# Sheet1.net
KiCad netlist of a schematic drawn in Altium Designer
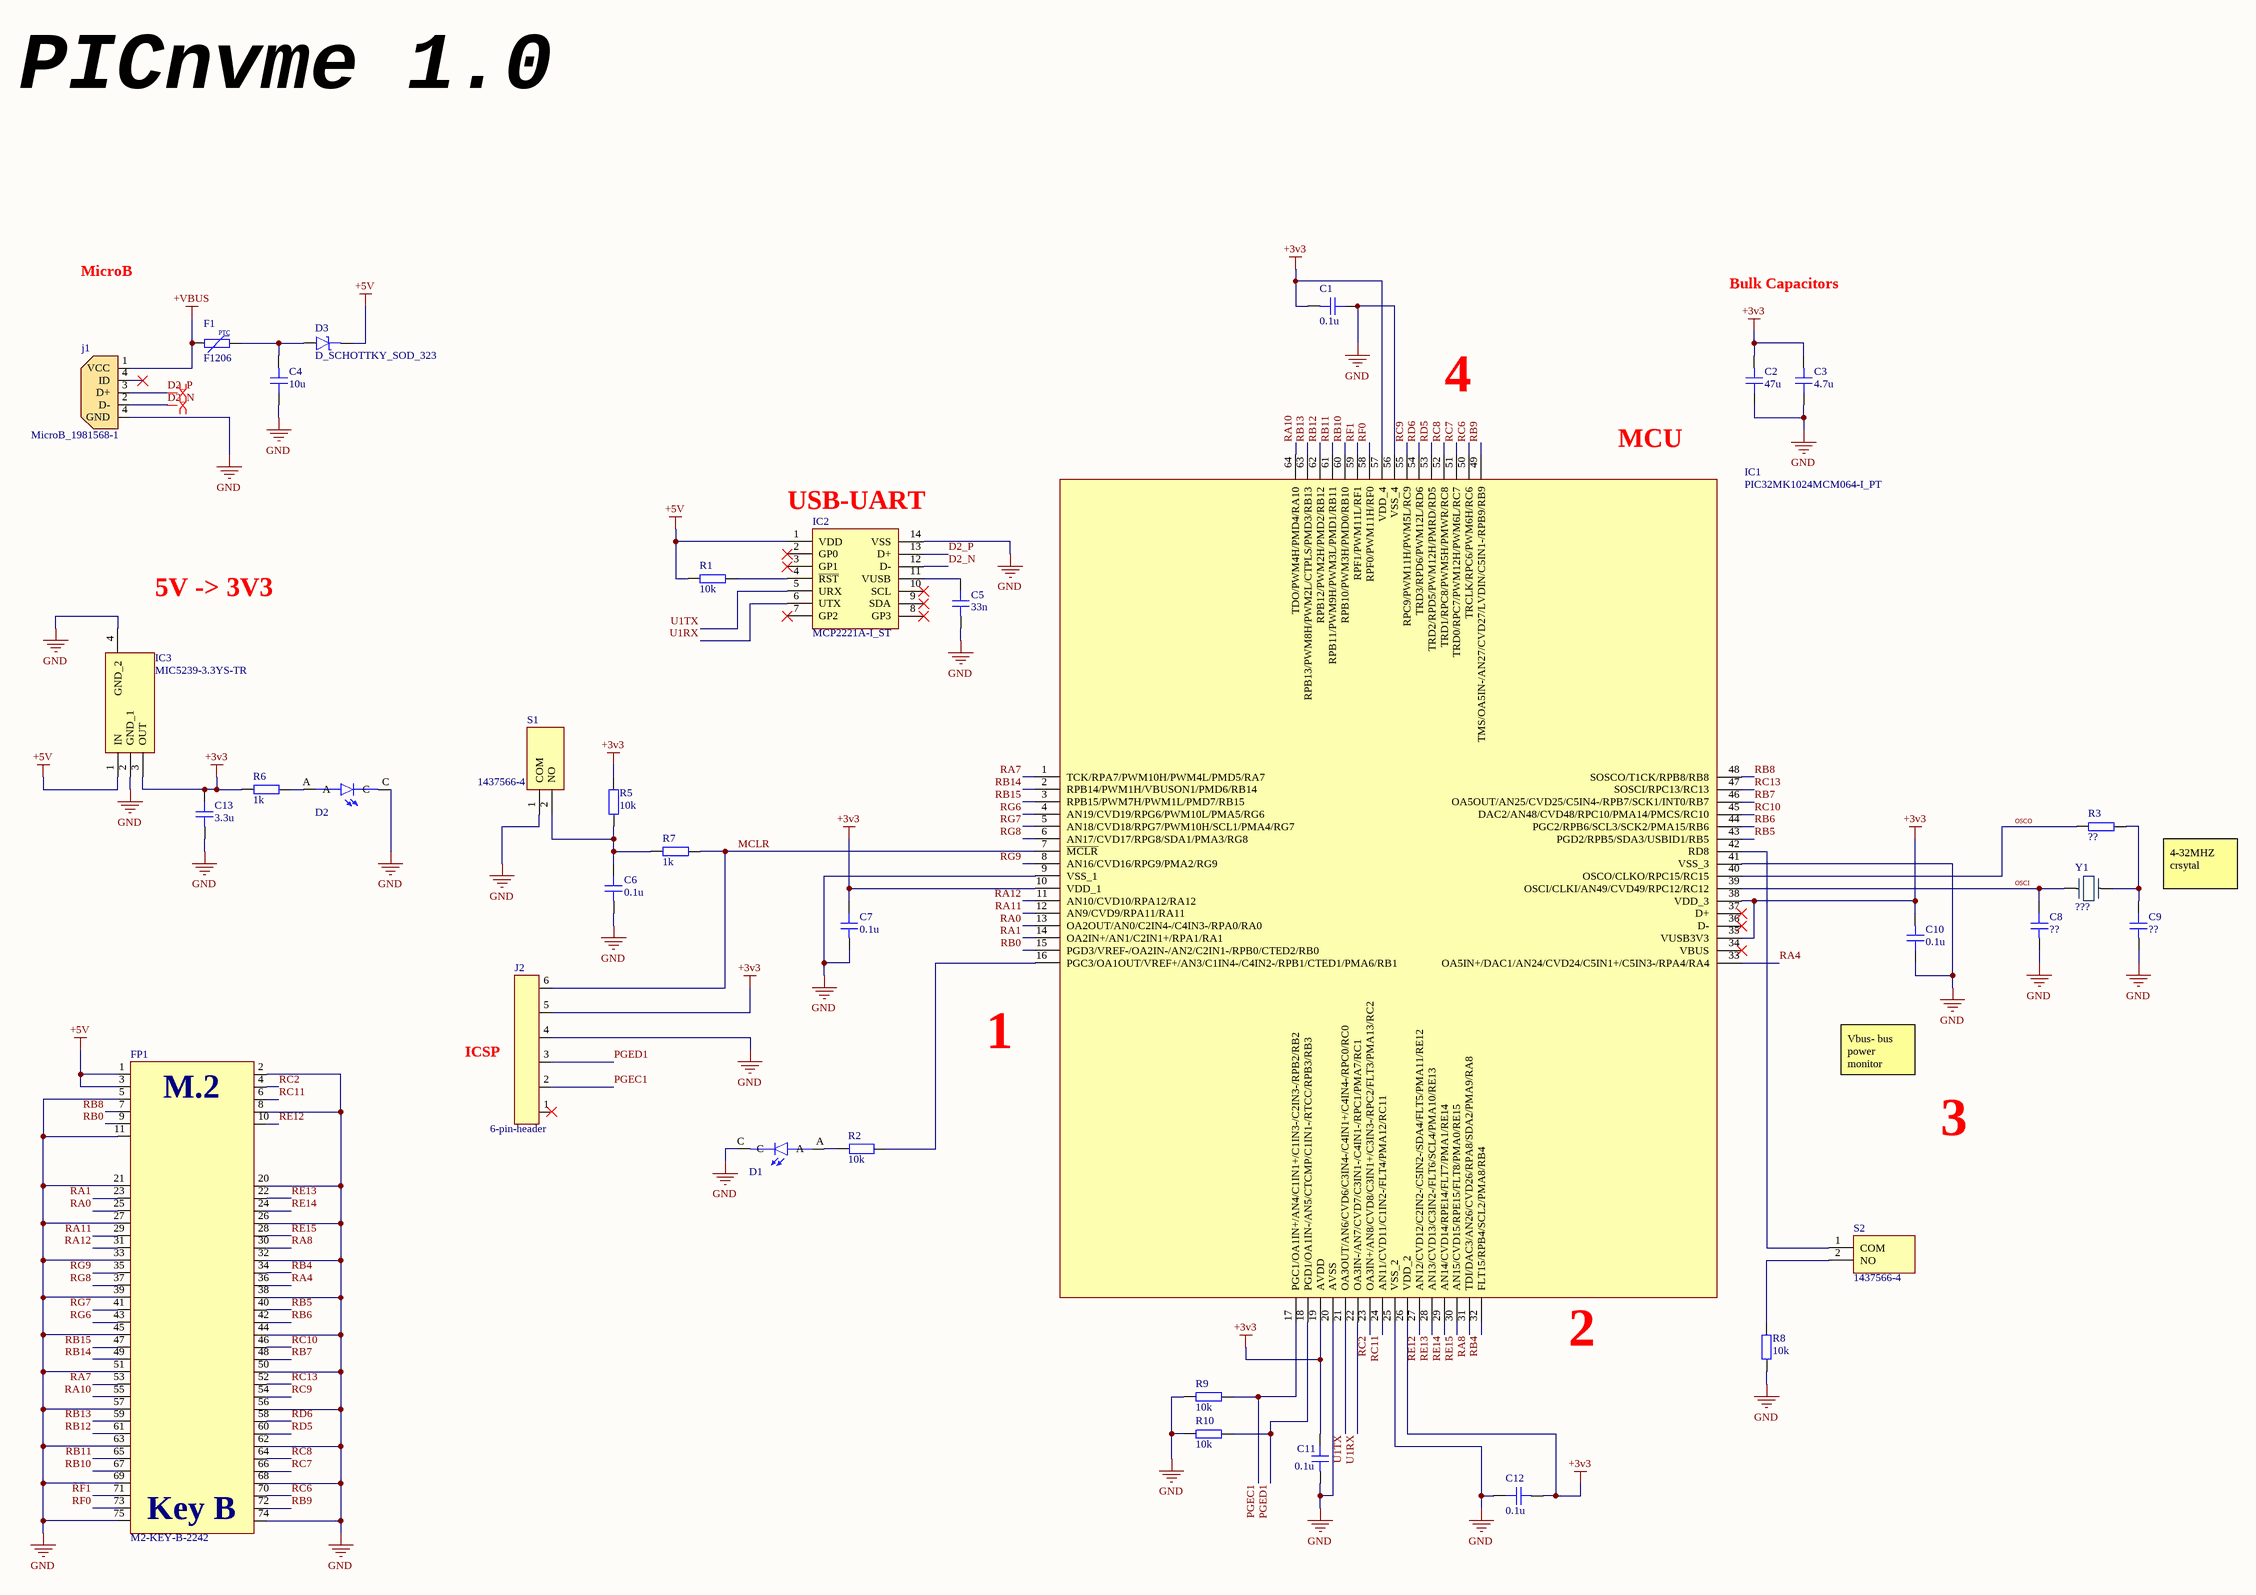
[diagram p0: Sheet1.SchDoc]

(export (version "E")
  (design (tool "Eeschema 10.0.6"))
  (components
    (comp (ref "C1")
      (value "0.1u")
      (footprint "CAP_0805")
      (description "Capacitor SMD 0805 16V")
      (libsource (lib "Pedro_Integrated_Library") (part "CAP_0805_16V"))
    )
    (comp (ref "C2")
      (value "47u")
      (footprint "CAP_0805")
      (description "Capacitor SMD 0805 16V")
      (libsource (lib "Pedro_Integrated_Library") (part "CAP_0805_16V"))
    )
    (comp (ref "C3")
      (value "4.7u")
      (footprint "CAP_0805")
      (description "Capacitor SMD 0805 16V")
      (libsource (lib "Pedro_Integrated_Library") (part "CAP_0805_16V"))
    )
    (comp (ref "C4")
      (value "10u")
      (footprint "CAP_0805")
      (description "Capacitor SMD 0805 10V")
      (libsource (lib "Schematic-Lib-PhilsLab") (part "CAP_0805_10V"))
    )
    (comp (ref "C5")
      (value "33n")
      (footprint "CAP_0805")
      (description "Capacitor SMD 0805 10V")
      (libsource (lib "Schematic-Lib-PhilsLab") (part "CAP_0805_10V"))
    )
    (comp (ref "C6")
      (value "0.1u")
      (footprint "CAP_0805")
      (description "Capacitor SMD 0805 16V")
      (libsource (lib "Pedro_Integrated_Library") (part "CAP_0805_16V"))
    )
    (comp (ref "C7")
      (value "0.1u")
      (footprint "CAP_0805")
      (description "Capacitor SMD 0805 16V")
      (libsource (lib "Pedro_Integrated_Library") (part "CAP_0805_16V"))
    )
    (comp (ref "C8")
      (value "??")
      (footprint "CAP_0805")
      (description "Capacitor SMD 0805 16V")
      (libsource (lib "Pedro_Integrated_Library") (part "CAP_0805_16V"))
    )
    (comp (ref "C9")
      (value "??")
      (footprint "CAP_0805")
      (description "Capacitor SMD 0805 16V")
      (libsource (lib "Pedro_Integrated_Library") (part "CAP_0805_16V"))
    )
    (comp (ref "C10")
      (value "0.1u")
      (footprint "CAP_0805")
      (description "Capacitor SMD 0805 16V")
      (libsource (lib "Pedro_Integrated_Library") (part "CAP_0805_16V"))
    )
    (comp (ref "C11")
      (value "0.1u")
      (footprint "CAP_0805")
      (description "Capacitor SMD 0805 16V")
      (libsource (lib "Pedro_Integrated_Library") (part "CAP_0805_16V"))
    )
    (comp (ref "C12")
      (value "0.1u")
      (footprint "CAP_0805")
      (description "Capacitor SMD 0805 16V")
      (libsource (lib "Pedro_Integrated_Library") (part "CAP_0805_16V"))
    )
    (comp (ref "C13")
      (value "3.3u")
      (footprint "CAP_0805")
      (description "Capacitor SMD 0805 16V")
      (libsource (lib "Pedro_Integrated_Library") (part "CAP_0805_16V"))
    )
    (comp (ref "D1")
      (value "SML-LXT0805IW-TR")
      (footprint "LEDC2012X120N")
      (description "Red - LED Indication - Discrete 2V 0805 (2012 Metric)")
      (fields (field (name "MF") "Lumex Opto/Components"))
      (libsource (lib "SML-LXT0805IW-TR") (part "SML-LXT0805IW-TR"))
    )
    (comp (ref "D2")
      (value "SML-LXT0805IW-TR")
      (footprint "LEDC2012X120N")
      (description "Red - LED Indication - Discrete 2V 0805 (2012 Metric)")
      (fields (field (name "MF") "Lumex Opto/Components"))
      (libsource (lib "SML-LXT0805IW-TR") (part "SML-LXT0805IW-TR"))
    )
    (comp (ref "D3")
      (value "D_SCHOTTKY_SOD_323")
      (footprint "SOD-323")
      (description "Diode Schottky SMD SOD-323")
      (libsource (lib "PhilsLab") (part "D_SCHOTTKY_SOD_323"))
    )
    (comp (ref "F1")
      (value "F1206")
      (footprint "FUSE_1206")
      (description "Fuse PPTC SMD 1206")
      (libsource (lib "Schematic-Lib-PhilsLab") (part "FUSE_PPTC_1206"))
    )
    (comp (ref "FP1")
      (value "M2-KEY-B-2242")
      (footprint "M2-KEY-B-2242")
      (description "M.2 Key B 22x42 Footprint")
      (libsource (lib "PhilsLab") (part "M2-KEY-B-2242"))
    )
    (comp (ref "IC1")
      (value "PIC32MK1024MCM064-I_PT")
      (footprint "QFP50P1200X1200X120-64N")
      (description "Integrated Circuit")
      (fields
        (field (name "MANUFACTURER_PART_NUMBER") "PIC32MK1024MCM064-I/PT")
        (field (name "MOUSER PART NUMBER") "579-2MK1024MCM064IPT")
      )
      (libsource (lib "Pedro_Integrated_Library") (part "PIC32MK1024MCM064-I_PT"))
    )
    (comp (ref "IC2")
      (value "MCP2221A-I_ST")
      (footprint "Pedro_pcb_lib:SOP65P640X120-14N")
      (description "Integrated Circuit")
      (fields
        (field (name "MANUFACTURER_PART_NUMBER") "MCP2221A-I/ST")
        (field (name "MOUSER PART NUMBER") "579-MCP2221A-I/ST")
      )
      (libsource (lib "*") (part "MCP2221A-I_ST"))
    )
    (comp (ref "IC3")
      (value "MIC5239-3.3YS-TR")
      (footprint "Pedro_pcb_lib:SOT230P700X180-4N")
      (description "Integrated Circuit")
      (fields (field (name "MOUSER PART NUMBER") "998-MIC5239-3.3YSTR"))
      (libsource (lib "*") (part "MIC5239-3.3YS-TR"))
    )
    (comp (ref "j1")
      (value "MicroB_1981568-1")
      (footprint "1981568-1")
      (libsource (lib "Pedro_Integrated_Library") (part "Micro_B"))
    )
    (comp (ref "J2")
      (value "6-pin-header")
      (footprint "G800W302018EU")
      (description "Pin Header 6 Position 2.54mm Pitch")
      (fields
        (field (name "MANUFACTURER") "Amphenol")
        (field (name "MANUFACTURER PART NUMBER") "G800W302018EU")
      )
      (libsource (lib "PhilsLab") (part "G800W302018EU"))
    )
    (comp (ref "R1")
      (value "10k")
      (footprint "RES_0805")
      (description "Resistor SMD 0805")
      (libsource (lib "Pedro_Integrated_Library") (part "RES_0805"))
    )
    (comp (ref "R2")
      (value "10k")
      (footprint "RES_0805")
      (description "Resistor SMD 0805")
      (libsource (lib "Pedro_Integrated_Library") (part "RES_0805"))
    )
    (comp (ref "R3")
      (value "??")
      (footprint "RES_0805")
      (description "Resistor SMD 0805")
      (libsource (lib "Pedro_Integrated_Library") (part "RES_0805"))
    )
    (comp (ref "R5")
      (value "10k")
      (footprint "RES_0805")
      (description "Resistor SMD 0805")
      (libsource (lib "Pedro_Integrated_Library") (part "RES_0805"))
    )
    (comp (ref "R6")
      (value "1k")
      (footprint "RES_0805")
      (description "Resistor SMD 0805")
      (libsource (lib "Pedro_Integrated_Library") (part "RES_0805"))
    )
    (comp (ref "R7")
      (value "1k")
      (footprint "RES_0805")
      (description "Resistor SMD 0805")
      (libsource (lib "Pedro_Integrated_Library") (part "RES_0805"))
    )
    (comp (ref "R8")
      (value "10k")
      (footprint "RES_0805")
      (description "Resistor SMD 0805")
      (libsource (lib "Pedro_Integrated_Library") (part "RES_0805"))
    )
    (comp (ref "R9")
      (value "10k")
      (footprint "RES_0805")
      (description "Resistor SMD 0805")
      (libsource (lib "Pedro_Integrated_Library") (part "RES_0805"))
    )
    (comp (ref "R10")
      (value "10k")
      (footprint "RES_0805")
      (description "Resistor SMD 0805")
      (libsource (lib "Pedro_Integrated_Library") (part "RES_0805"))
    )
    (comp (ref "S1")
      (value "1437566-4")
      (footprint "Pedro_pcb_lib:14375664")
      (description "Switch")
      (libsource (lib "Pedro_sch_lib") (part "1437566-4"))
    )
    (comp (ref "S2")
      (value "1437566-4")
      (footprint "Pedro_pcb_lib:14375664")
      (description "Switch")
      (libsource (lib "") (part "1437566-4_1"))
    )
    (comp (ref "Y1")
      (value "???")
      (footprint "ABM38000MHZC4T")
      (libsource (lib "Pedro_Integrated_Library") (part "Crystal_SMD"))
    )
  )
  (nets
    (net (code "1") (name "+3v3") (class "Default")
      (node (ref "C1") (pin "1") (pinfunction "1_1") (pintype "passive"))
      (node (ref "C10") (pin "1") (pinfunction "1_1") (pintype "passive"))
      (node (ref "C11") (pin "2") (pinfunction "2_2") (pintype "passive"))
      (node (ref "C12") (pin "1") (pinfunction "1_1") (pintype "passive"))
      (node (ref "C13") (pin "2") (pinfunction "2_2") (pintype "passive"))
      (node (ref "C2") (pin "1") (pinfunction "1_1") (pintype "passive"))
      (node (ref "C3") (pin "1") (pinfunction "1_1") (pintype "passive"))
      (node (ref "C7") (pin "2") (pinfunction "2_2") (pintype "passive"))
      (node (ref "IC1") (pin "10") (pinfunction "VDD_1_10") (pintype "passive"))
      (node (ref "IC1") (pin "19") (pinfunction "AVDD_19") (pintype "passive"))
      (node (ref "IC1") (pin "26") (pinfunction "VDD_2_26") (pintype "passive"))
      (node (ref "IC1") (pin "35") (pinfunction "VUSB3V3_35") (pintype "passive"))
      (node (ref "IC1") (pin "38") (pinfunction "VDD_3_38") (pintype "passive"))
      (node (ref "IC1") (pin "57") (pinfunction "VDD_4_57") (pintype "passive"))
      (node (ref "IC3") (pin "3") (pinfunction "OUT_3") (pintype "passive"))
      (node (ref "J2") (pin "5") (pinfunction "5_5") (pintype "passive"))
      (node (ref "R5") (pin "1") (pinfunction "1_1") (pintype "passive"))
      (node (ref "R6") (pin "2") (pinfunction "2_2") (pintype "passive"))
    )
    (net (code "2") (name "+5V") (class "Default")
      (node (ref "D3") (pin "K") (pinfunction "K_K") (pintype "passive"))
      (node (ref "FP1") (pin "1") (pintype "passive"))
      (node (ref "FP1") (pin "3") (pintype "passive"))
      (node (ref "IC2") (pin "1") (pinfunction "VDD_1") (pintype "passive"))
      (node (ref "IC3") (pin "1") (pinfunction "IN_1") (pintype "passive"))
      (node (ref "R1") (pin "1") (pinfunction "1_1") (pintype "passive"))
    )
    (net (code "3") (name "+VBUS") (class "Default")
      (node (ref "F1") (pin "1") (pinfunction "1_1") (pintype "passive"))
      (node (ref "j1") (pin "1") (pinfunction "VCC_1") (pintype "power_in"))
    )
    (net (code "4") (name "/D2_N") (class "Default")
      (node (ref "IC2") (pin "12") (pinfunction "D-_12") (pintype "passive"))
      (node (ref "j1") (pin "2") (pinfunction "D-_2") (pintype "bidirectional"))
    )
    (net (code "5") (name "/D2_P") (class "Default")
      (node (ref "IC2") (pin "13") (pinfunction "D+_13") (pintype "passive"))
      (node (ref "j1") (pin "3") (pinfunction "D+_3") (pintype "bidirectional"))
    )
    (net (code "6") (name "/MCLR") (class "Default")
      (node (ref "IC1") (pin "7") (pinfunction "~{MCLR}_7") (pintype "passive"))
      (node (ref "J2") (pin "6") (pinfunction "6_6") (pintype "passive"))
      (node (ref "R7") (pin "1") (pinfunction "1_1") (pintype "passive"))
    )
    (net (code "7") (name "/OSCI") (class "Default")
      (node (ref "C8") (pin "2") (pinfunction "2_2") (pintype "passive"))
      (node (ref "IC1") (pin "39") (pinfunction "OSCI/CLKI/AN49/CVD49/RPC12/RC12_39") (pintype "passive"))
      (node (ref "Y1") (pin "1") (pinfunction "1_1") (pintype "passive"))
    )
    (net (code "8") (name "/OSCO") (class "Default")
      (node (ref "IC1") (pin "40") (pinfunction "OSCO/CLKO/RPC15/RC15_40") (pintype "passive"))
      (node (ref "R3") (pin "2") (pinfunction "2_2") (pintype "passive"))
    )
    (net (code "9") (name "/PGEC1") (class "Default")
      (node (ref "IC1") (pin "17") (pinfunction "PGC1/OA1IN+/AN4/C1IN1+/C1IN3-/C2IN3-/RPB2/RB2_17") (pintype "passive"))
      (node (ref "J2") (pin "2") (pinfunction "2_2") (pintype "passive"))
      (node (ref "R9") (pin "1") (pinfunction "1_1") (pintype "passive"))
    )
    (net (code "10") (name "/PGED1") (class "Default")
      (node (ref "IC1") (pin "18") (pinfunction "PGD1/OA1IN-/AN5/CTCMP/C1IN1-/RTCC/RPB3/RB3_18") (pintype "passive"))
      (node (ref "J2") (pin "3") (pinfunction "3_3") (pintype "passive"))
      (node (ref "R10") (pin "1") (pinfunction "1_1") (pintype "passive"))
    )
    (net (code "11") (name "/RA0") (class "Default")
      (node (ref "FP1") (pin "25") (pintype "passive"))
      (node (ref "IC1") (pin "13") (pinfunction "OA2OUT/AN0/C2IN4-/C4IN3-/RPA0/RA0_13") (pintype "passive"))
    )
    (net (code "12") (name "/RA1") (class "Default")
      (node (ref "FP1") (pin "23") (pintype "passive"))
      (node (ref "IC1") (pin "14") (pinfunction "OA2IN+/AN1/C2IN1+/RPA1/RA1_14") (pintype "passive"))
    )
    (net (code "13") (name "/RA4") (class "Default")
      (node (ref "FP1") (pin "36") (pintype "passive"))
      (node (ref "IC1") (pin "33") (pinfunction "OA5IN+/DAC1/AN24/CVD24/C5IN1+/C5IN3-/RPA4/RA4_33") (pintype "passive"))
    )
    (net (code "14") (name "/RA7") (class "Default")
      (node (ref "FP1") (pin "53") (pintype "passive"))
      (node (ref "IC1") (pin "1") (pinfunction "TCK/RPA7/PWM10H/PWM4L/PMD5/RA7_1") (pintype "passive"))
    )
    (net (code "15") (name "/RA8") (class "Default")
      (node (ref "FP1") (pin "30") (pintype "passive"))
      (node (ref "IC1") (pin "31") (pinfunction "TDI/DAC3/AN26/CVD26/RPA8/SDA2/PMA9/RA8_31") (pintype "passive"))
    )
    (net (code "16") (name "/RA10") (class "Default")
      (node (ref "FP1") (pin "55") (pintype "passive"))
      (node (ref "IC1") (pin "64") (pinfunction "TDO/PWM4H/PMD4/RA10_64") (pintype "passive"))
    )
    (net (code "17") (name "/RA11") (class "Default")
      (node (ref "FP1") (pin "29") (pintype "passive"))
      (node (ref "IC1") (pin "12") (pinfunction "AN9/CVD9/RPA11/RA11_12") (pintype "passive"))
    )
    (net (code "18") (name "/RA12") (class "Default")
      (node (ref "FP1") (pin "31") (pintype "passive"))
      (node (ref "IC1") (pin "11") (pinfunction "AN10/CVD10/RPA12/RA12_11") (pintype "passive"))
    )
    (net (code "19") (name "/RB0") (class "Default")
      (node (ref "FP1") (pin "9") (pintype "passive"))
      (node (ref "IC1") (pin "15") (pinfunction "PGD3/VREF-/OA2IN-/AN2/C2IN1-/RPB0/CTED2/RB0_15") (pintype "passive"))
    )
    (net (code "20") (name "/RB4") (class "Default")
      (node (ref "FP1") (pin "34") (pintype "passive"))
      (node (ref "IC1") (pin "32") (pinfunction "FLT15/RPB4/SCL2/PMA8/RB4_32") (pintype "passive"))
    )
    (net (code "21") (name "/RB5") (class "Default")
      (node (ref "FP1") (pin "40") (pintype "passive"))
      (node (ref "IC1") (pin "43") (pinfunction "PGD2/RPB5/SDA3/USBID1/RB5_43") (pintype "passive"))
    )
    (net (code "22") (name "/RB6") (class "Default")
      (node (ref "FP1") (pin "42") (pintype "passive"))
      (node (ref "IC1") (pin "44") (pinfunction "PGC2/RPB6/SCL3/SCK2/PMA15/RB6_44") (pintype "passive"))
    )
    (net (code "23") (name "/RB7") (class "Default")
      (node (ref "FP1") (pin "48") (pintype "passive"))
      (node (ref "IC1") (pin "46") (pinfunction "OA5OUT/AN25/CVD25/C5IN4-/RPB7/SCK1/INT0/RB7_46") (pintype "passive"))
    )
    (net (code "24") (name "/RB8") (class "Default")
      (node (ref "FP1") (pin "7") (pintype "passive"))
      (node (ref "IC1") (pin "48") (pinfunction "SOSCO/T1CK/RPB8/RB8_48") (pintype "passive"))
    )
    (net (code "25") (name "/RB9") (class "Default")
      (node (ref "FP1") (pin "72") (pintype "passive"))
      (node (ref "IC1") (pin "49") (pinfunction "TMS/OA5IN-/AN27/CVD27/LVDIN/C5IN1-/RPB9/RB9_49") (pintype "passive"))
    )
    (net (code "26") (name "/RB10") (class "Default")
      (node (ref "FP1") (pin "67") (pintype "passive"))
      (node (ref "IC1") (pin "60") (pinfunction "RPB10/PWM3H/PMD0/RB10_60") (pintype "passive"))
    )
    (net (code "27") (name "/RB11") (class "Default")
      (node (ref "FP1") (pin "65") (pintype "passive"))
      (node (ref "IC1") (pin "61") (pinfunction "RPB11/PWM9H/PWM3L/PMD1/RB11_61") (pintype "passive"))
    )
    (net (code "28") (name "/RB12") (class "Default")
      (node (ref "FP1") (pin "61") (pintype "passive"))
      (node (ref "IC1") (pin "62") (pinfunction "RPB12/PWM2H/PMD2/RB12_62") (pintype "passive"))
    )
    (net (code "29") (name "/RB13") (class "Default")
      (node (ref "FP1") (pin "59") (pintype "passive"))
      (node (ref "IC1") (pin "63") (pinfunction "RPB13/PWM8H/PWM2L/CTPLS/PMD3/RB13_63") (pintype "passive"))
    )
    (net (code "30") (name "/RB14") (class "Default")
      (node (ref "FP1") (pin "49") (pintype "passive"))
      (node (ref "IC1") (pin "2") (pinfunction "RPB14/PWM1H/VBUSON1/PMD6/RB14_2") (pintype "passive"))
    )
    (net (code "31") (name "/RB15") (class "Default")
      (node (ref "FP1") (pin "47") (pintype "passive"))
      (node (ref "IC1") (pin "3") (pinfunction "RPB15/PWM7H/PWM1L/PMD7/RB15_3") (pintype "passive"))
    )
    (net (code "32") (name "/RC2") (class "Default")
      (node (ref "FP1") (pin "4") (pintype "passive"))
      (node (ref "IC1") (pin "23") (pinfunction "OA3IN+/AN8/CVD8/C3IN1+/C3IN3-/RPC2/FLT3/PMA13/RC2_23") (pintype "passive"))
    )
    (net (code "33") (name "/RC6") (class "Default")
      (node (ref "FP1") (pin "70") (pintype "passive"))
      (node (ref "IC1") (pin "50") (pinfunction "TRCLK/RPC6/PWM6H/RC6_50") (pintype "passive"))
    )
    (net (code "34") (name "/RC7") (class "Default")
      (node (ref "FP1") (pin "66") (pintype "passive"))
      (node (ref "IC1") (pin "51") (pinfunction "TRD0/RPC7/PWM12H/PWM6L/RC7_51") (pintype "passive"))
    )
    (net (code "35") (name "/RC8") (class "Default")
      (node (ref "FP1") (pin "64") (pintype "passive"))
      (node (ref "IC1") (pin "52") (pinfunction "TRD1/RPC8/PWM5H/PMWR/RC8_52") (pintype "passive"))
    )
    (net (code "36") (name "/RC9") (class "Default")
      (node (ref "FP1") (pin "54") (pintype "passive"))
      (node (ref "IC1") (pin "55") (pinfunction "RPC9/PWM11H/PWM5L/RC9_55") (pintype "passive"))
    )
    (net (code "37") (name "/RC10") (class "Default")
      (node (ref "FP1") (pin "46") (pintype "passive"))
      (node (ref "IC1") (pin "45") (pinfunction "DAC2/AN48/CVD48/RPC10/PMA14/PMCS/RC10_45") (pintype "passive"))
    )
    (net (code "38") (name "/RC11") (class "Default")
      (node (ref "FP1") (pin "6") (pintype "passive"))
      (node (ref "IC1") (pin "24") (pinfunction "AN11/CVD11/C1IN2-/FLT4/PMA12/RC11_24") (pintype "passive"))
    )
    (net (code "39") (name "/RC13") (class "Default")
      (node (ref "FP1") (pin "52") (pintype "passive"))
      (node (ref "IC1") (pin "47") (pinfunction "SOSCI/RPC13/RC13_47") (pintype "passive"))
    )
    (net (code "40") (name "/RD5") (class "Default")
      (node (ref "FP1") (pin "60") (pintype "passive"))
      (node (ref "IC1") (pin "53") (pinfunction "TRD2/RPD5/PWM12H/PMRD/RD5_53") (pintype "passive"))
    )
    (net (code "41") (name "/RD6") (class "Default")
      (node (ref "FP1") (pin "58") (pintype "passive"))
      (node (ref "IC1") (pin "54") (pinfunction "TRD3/RPD6/PWM12L/RD6_54") (pintype "passive"))
    )
    (net (code "42") (name "/RE12") (class "Default")
      (node (ref "FP1") (pin "10") (pintype "passive"))
      (node (ref "IC1") (pin "27") (pinfunction "AN12/CVD12/C2IN2-/C5IN2-/SDA4/FLT5/PMA11/RE12_27") (pintype "passive"))
    )
    (net (code "43") (name "/RE13") (class "Default")
      (node (ref "FP1") (pin "22") (pintype "passive"))
      (node (ref "IC1") (pin "28") (pinfunction "AN13/CVD13/C3IN2-/FLT6/SCL4/PMA10/RE13_28") (pintype "passive"))
    )
    (net (code "44") (name "/RE14") (class "Default")
      (node (ref "FP1") (pin "24") (pintype "passive"))
      (node (ref "IC1") (pin "29") (pinfunction "AN14/CVD14/RPE14/FLT7/PMA1/RE14_29") (pintype "passive"))
    )
    (net (code "45") (name "/RE15") (class "Default")
      (node (ref "FP1") (pin "28") (pintype "passive"))
      (node (ref "IC1") (pin "30") (pinfunction "AN15/CVD15/RPE15/FLT8/PMA0/RE15_30") (pintype "passive"))
    )
    (net (code "46") (name "/RF0") (class "Default")
      (node (ref "FP1") (pin "73") (pintype "passive"))
      (node (ref "IC1") (pin "58") (pinfunction "RPF0/PWM11H/RF0_58") (pintype "passive"))
    )
    (net (code "47") (name "/RF1") (class "Default")
      (node (ref "FP1") (pin "71") (pintype "passive"))
      (node (ref "IC1") (pin "59") (pinfunction "RPF1/PWM11L/RF1_59") (pintype "passive"))
    )
    (net (code "48") (name "/RG6") (class "Default")
      (node (ref "FP1") (pin "43") (pintype "passive"))
      (node (ref "IC1") (pin "4") (pinfunction "AN19/CVD19/RPG6/PWM10L/PMA5/RG6_4") (pintype "passive"))
    )
    (net (code "49") (name "/RG7") (class "Default")
      (node (ref "FP1") (pin "41") (pintype "passive"))
      (node (ref "IC1") (pin "5") (pinfunction "AN18/CVD18/RPG7/PWM10H/SCL1/PMA4/RG7_5") (pintype "passive"))
    )
    (net (code "50") (name "/RG8") (class "Default")
      (node (ref "FP1") (pin "37") (pintype "passive"))
      (node (ref "IC1") (pin "6") (pinfunction "AN17/CVD17/RPG8/SDA1/PMA3/RG8_6") (pintype "passive"))
    )
    (net (code "51") (name "/RG9") (class "Default")
      (node (ref "FP1") (pin "35") (pintype "passive"))
      (node (ref "IC1") (pin "8") (pinfunction "AN16/CVD16/RPG9/PMA2/RG9_8") (pintype "passive"))
    )
    (net (code "52") (name "/U1RX") (class "Default")
      (node (ref "IC1") (pin "22") (pinfunction "OA3IN-/AN7/CVD7/C3IN1-/C4IN1-/RPC1/PMA7/RC1_22") (pintype "passive"))
      (node (ref "IC2") (pin "6") (pinfunction "UTX_6") (pintype "passive"))
    )
    (net (code "53") (name "/U1TX") (class "Default")
      (node (ref "IC1") (pin "21") (pinfunction "OA3OUT/AN6/CVD6/C3IN4-/C4IN1+/C4IN4-/RPC0/RC0_21") (pintype "passive"))
      (node (ref "IC2") (pin "5") (pinfunction "URX_5") (pintype "passive"))
    )
    (net (code "54") (name "GND") (class "Default")
      (node (ref "C1") (pin "2") (pinfunction "2_2") (pintype "passive"))
      (node (ref "C10") (pin "2") (pinfunction "2_2") (pintype "passive"))
      (node (ref "C11") (pin "1") (pinfunction "1_1") (pintype "passive"))
      (node (ref "C12") (pin "2") (pinfunction "2_2") (pintype "passive"))
      (node (ref "C13") (pin "1") (pinfunction "1_1") (pintype "passive"))
      (node (ref "C2") (pin "2") (pinfunction "2_2") (pintype "passive"))
      (node (ref "C3") (pin "2") (pinfunction "2_2") (pintype "passive"))
      (node (ref "C4") (pin "2") (pinfunction "2_2") (pintype "passive"))
      (node (ref "C5") (pin "1") (pinfunction "1_1") (pintype "passive"))
      (node (ref "C6") (pin "1") (pinfunction "1_1") (pintype "passive"))
      (node (ref "C7") (pin "1") (pinfunction "1_1") (pintype "passive"))
      (node (ref "C8") (pin "1") (pinfunction "1_1") (pintype "passive"))
      (node (ref "C9") (pin "1") (pinfunction "1_1") (pintype "passive"))
      (node (ref "D1") (pin "C") (pinfunction "C_C") (pintype "passive"))
      (node (ref "D2") (pin "C") (pinfunction "C_C") (pintype "passive"))
      (node (ref "FP1") (pin "11") (pintype "passive"))
      (node (ref "FP1") (pin "2") (pintype "passive"))
      (node (ref "FP1") (pin "20") (pintype "passive"))
      (node (ref "FP1") (pin "21") (pintype "passive"))
      (node (ref "FP1") (pin "26") (pintype "passive"))
      (node (ref "FP1") (pin "27") (pintype "passive"))
      (node (ref "FP1") (pin "32") (pintype "passive"))
      (node (ref "FP1") (pin "33") (pintype "passive"))
      (node (ref "FP1") (pin "38") (pintype "passive"))
      (node (ref "FP1") (pin "39") (pintype "passive"))
      (node (ref "FP1") (pin "44") (pintype "passive"))
      (node (ref "FP1") (pin "45") (pintype "passive"))
      (node (ref "FP1") (pin "5") (pintype "passive"))
      (node (ref "FP1") (pin "50") (pintype "passive"))
      (node (ref "FP1") (pin "51") (pintype "passive"))
      (node (ref "FP1") (pin "56") (pintype "passive"))
      (node (ref "FP1") (pin "57") (pintype "passive"))
      (node (ref "FP1") (pin "62") (pintype "passive"))
      (node (ref "FP1") (pin "63") (pintype "passive"))
      (node (ref "FP1") (pin "68") (pintype "passive"))
      (node (ref "FP1") (pin "69") (pintype "passive"))
      (node (ref "FP1") (pin "74") (pintype "passive"))
      (node (ref "FP1") (pin "75") (pintype "passive"))
      (node (ref "FP1") (pin "8") (pintype "passive"))
      (node (ref "IC1") (pin "20") (pinfunction "AVSS_20") (pintype "passive"))
      (node (ref "IC1") (pin "25") (pinfunction "VSS_2_25") (pintype "passive"))
      (node (ref "IC1") (pin "41") (pinfunction "VSS_3_41") (pintype "passive"))
      (node (ref "IC1") (pin "56") (pinfunction "VSS_4_56") (pintype "passive"))
      (node (ref "IC1") (pin "9") (pinfunction "VSS_1_9") (pintype "passive"))
      (node (ref "IC2") (pin "14") (pinfunction "VSS_14") (pintype "passive"))
      (node (ref "IC3") (pin "2") (pinfunction "GND_1_2") (pintype "passive"))
      (node (ref "IC3") (pin "4") (pinfunction "GND_2_4") (pintype "passive"))
      (node (ref "J2") (pin "4") (pinfunction "4_4") (pintype "passive"))
      (node (ref "R10") (pin "2") (pinfunction "2_2") (pintype "passive"))
      (node (ref "R8") (pin "2") (pinfunction "2_2") (pintype "passive"))
      (node (ref "R9") (pin "2") (pinfunction "2_2") (pintype "passive"))
      (node (ref "S1") (pin "1") (pinfunction "COM_1") (pintype "passive"))
      (node (ref "j1") (pin "4") (pinfunction "GND_4") (pintype "power_in"))
    )
    (net (code "55") (name "Net-(C4-Pad1)") (class "Default")
      (node (ref "C4") (pin "1") (pinfunction "1_1") (pintype "passive"))
      (node (ref "D3") (pin "A") (pinfunction "A_A") (pintype "passive"))
      (node (ref "F1") (pin "2") (pinfunction "2_2") (pintype "passive"))
    )
    (net (code "56") (name "Net-(C9-Pad2)") (class "Default")
      (node (ref "C9") (pin "2") (pinfunction "2_2") (pintype "passive"))
      (node (ref "R3") (pin "1") (pinfunction "1_1") (pintype "passive"))
      (node (ref "Y1") (pin "2") (pinfunction "2_2") (pintype "passive"))
    )
    (net (code "57") (name "Net-(D1-PadA)") (class "Default")
      (node (ref "D1") (pin "A") (pinfunction "A_A") (pintype "passive"))
      (node (ref "R2") (pin "2") (pinfunction "2_2") (pintype "passive"))
    )
    (net (code "58") (name "Net-(D2-PadA)") (class "Default")
      (node (ref "D2") (pin "A") (pinfunction "A_A") (pintype "passive"))
      (node (ref "R6") (pin "1") (pinfunction "1_1") (pintype "passive"))
    )
    (net (code "59") (name "Net-(IC1-PGC3{slash}OA1OUT{slash}VREF+{slash}AN3{slash}C1IN4-{slash}C4IN2-{slash}RPB1{slash}CTED1{slash}PMA6{slash}RB1)") (class "Default")
      (node (ref "IC1") (pin "16") (pinfunction "PGC3/OA1OUT/VREF+/AN3/C1IN4-/C4IN2-/RPB1/CTED1/PMA6/RB1_16") (pintype "passive"))
      (node (ref "R2") (pin "1") (pinfunction "1_1") (pintype "passive"))
    )
    (net (code "60") (name "Net-(IC1-RD8)") (class "Default")
      (node (ref "IC1") (pin "42") (pinfunction "RD8_42") (pintype "passive"))
      (node (ref "S2") (pin "1") (pinfunction "COM_1") (pintype "passive"))
    )
    (net (code "61") (name "Net-(IC2-VUSB)") (class "Default")
      (node (ref "C5") (pin "2") (pinfunction "2_2") (pintype "passive"))
      (node (ref "IC2") (pin "11") (pinfunction "VUSB_11") (pintype "passive"))
    )
    (net (code "62") (name "Net-(IC2-~{RST})") (class "Default")
      (node (ref "IC2") (pin "4") (pinfunction "~{RST}_4") (pintype "passive"))
      (node (ref "R1") (pin "2") (pinfunction "2_2") (pintype "passive"))
    )
    (net (code "63") (name "Net-(S1-NO)") (class "Default")
      (node (ref "C6") (pin "2") (pinfunction "2_2") (pintype "passive"))
      (node (ref "R5") (pin "2") (pinfunction "2_2") (pintype "passive"))
      (node (ref "R7") (pin "2") (pinfunction "2_2") (pintype "passive"))
      (node (ref "S1") (pin "2") (pinfunction "NO_2") (pintype "passive"))
    )
    (net (code "64") (name "Net-(S2-NO)") (class "Default")
      (node (ref "R8") (pin "1") (pinfunction "1_1") (pintype "passive"))
      (node (ref "S2") (pin "2") (pinfunction "NO_2") (pintype "passive"))
    )
    (net (code "65") (name "unconnected-(IC1-D+-Pad37)") (class "Default")
      (node (ref "IC1") (pin "37") (pinfunction "D+_37") (pintype "passive+no_connect"))
    )
    (net (code "66") (name "unconnected-(IC1-D--Pad36)") (class "Default")
      (node (ref "IC1") (pin "36") (pinfunction "D-_36") (pintype "passive+no_connect"))
    )
    (net (code "67") (name "unconnected-(IC1-VBUS-Pad34)") (class "Default")
      (node (ref "IC1") (pin "34") (pinfunction "VBUS_34") (pintype "passive+no_connect"))
    )
    (net (code "68") (name "unconnected-(IC2-GP0-Pad2)") (class "Default")
      (node (ref "IC2") (pin "2") (pinfunction "GP0_2") (pintype "passive+no_connect"))
    )
    (net (code "69") (name "unconnected-(IC2-GP1-Pad3)") (class "Default")
      (node (ref "IC2") (pin "3") (pinfunction "GP1_3") (pintype "passive+no_connect"))
    )
    (net (code "70") (name "unconnected-(IC2-GP2-Pad7)") (class "Default")
      (node (ref "IC2") (pin "7") (pinfunction "GP2_7") (pintype "passive+no_connect"))
    )
    (net (code "71") (name "unconnected-(IC2-GP3-Pad8)") (class "Default")
      (node (ref "IC2") (pin "8") (pinfunction "GP3_8") (pintype "passive+no_connect"))
    )
    (net (code "72") (name "unconnected-(IC2-SCL-Pad10)") (class "Default")
      (node (ref "IC2") (pin "10") (pinfunction "SCL_10") (pintype "passive+no_connect"))
    )
    (net (code "73") (name "unconnected-(IC2-SDA-Pad9)") (class "Default")
      (node (ref "IC2") (pin "9") (pinfunction "SDA_9") (pintype "passive+no_connect"))
    )
    (net (code "74") (name "unconnected-(J2-Pad1)") (class "Default")
      (node (ref "J2") (pin "1") (pinfunction "1_1") (pintype "passive+no_connect"))
    )
    (net (code "75") (name "unconnected-(j1-ID-Pad4)") (class "Default")
      (node (ref "j1") (pin "4") (pinfunction "ID_4") (pintype "passive+no_connect"))
    )
  )
)
